# portable-atmega.net
KiCad netlist of a schematic drawn in EAGLE
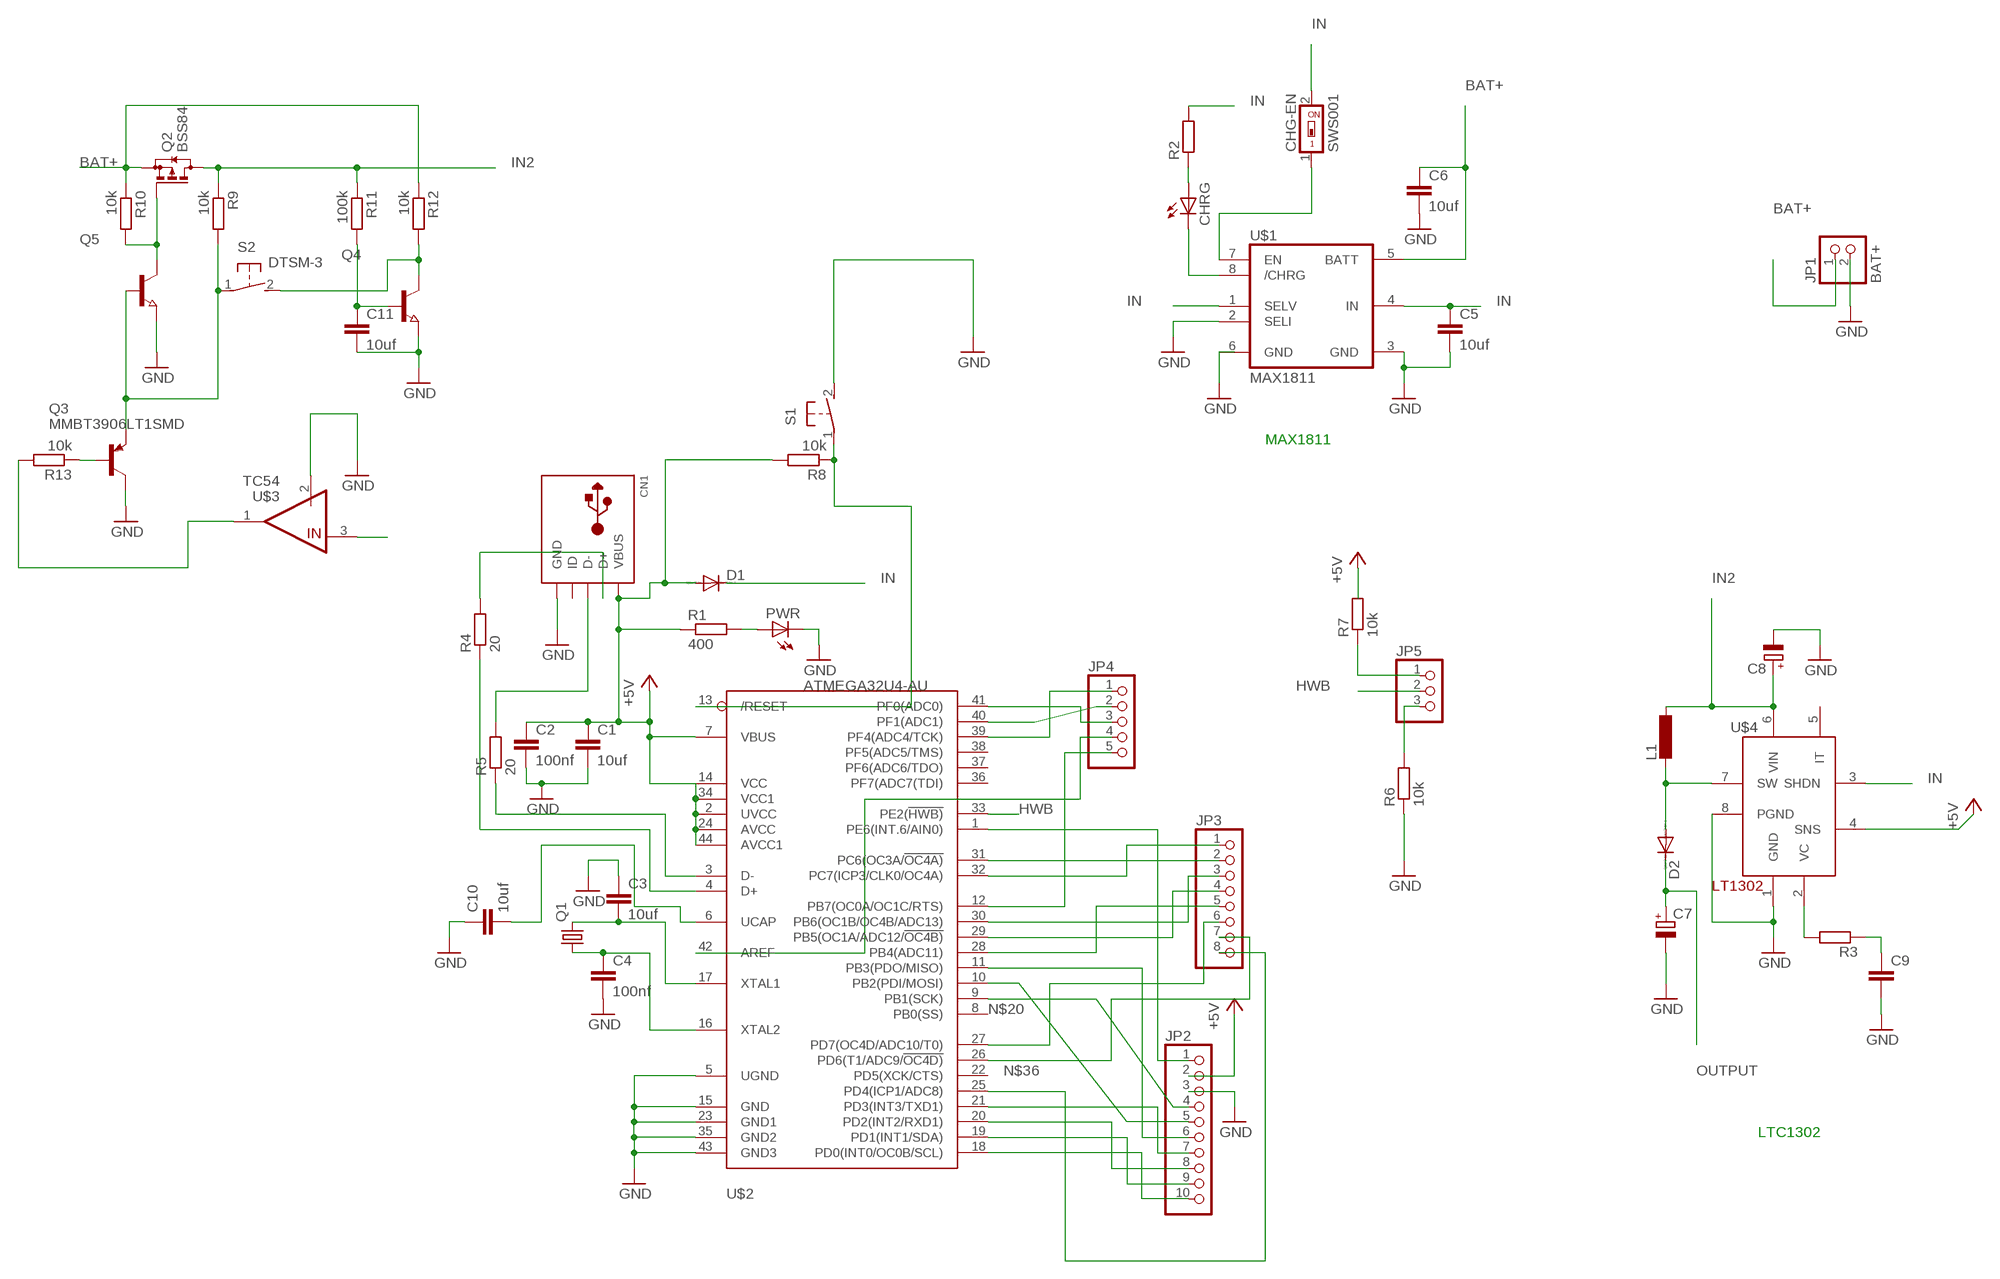
[diagram p0: schematic, sheet 1]

(export (version "E")
  (design (tool "Eeschema 10.0.6"))
  (components
    (comp (ref "C1")
      (value "10uf")
      (footprint "eagle-import:C1206")
      (libsource (lib "eagle-import") (part "C-EUC1206"))
    )
    (comp (ref "C2")
      (value "100nf")
      (footprint "eagle-import:C1206")
      (libsource (lib "eagle-import") (part "C-EUC1206"))
    )
    (comp (ref "C3")
      (value "10uf")
      (footprint "eagle-import:C1206")
      (libsource (lib "eagle-import") (part "C-EUC1206"))
    )
    (comp (ref "C4")
      (value "100nf")
      (footprint "eagle-import:C1206")
      (libsource (lib "eagle-import") (part "C-EUC1206"))
    )
    (comp (ref "C5")
      (value "10uf")
      (footprint "eagle-import:C1206")
      (libsource (lib "eagle-import") (part "C-EUC1206"))
    )
    (comp (ref "C6")
      (value "10uf")
      (footprint "eagle-import:C1206")
      (libsource (lib "eagle-import") (part "C-EUC1206"))
    )
    (comp (ref "C7")
      (value "CPOL-EUD")
      (footprint "eagle-import:PANASONIC_D")
      (libsource (lib "eagle-import") (part "CPOL-EUD"))
    )
    (comp (ref "C8")
      (value "CPOL-EUD")
      (footprint "eagle-import:PANASONIC_D")
      (libsource (lib "eagle-import") (part "CPOL-EUD"))
    )
    (comp (ref "C9")
      (value "C-EUC1206")
      (footprint "eagle-import:C1206")
      (libsource (lib "eagle-import") (part "C-EUC1206"))
    )
    (comp (ref "C10")
      (value "10uf")
      (footprint "eagle-import:C1206")
      (libsource (lib "eagle-import") (part "C-EUC1206"))
    )
    (comp (ref "C11")
      (value "10uf")
      (footprint "eagle-import:C1206")
      (libsource (lib "eagle-import") (part "C-EUC1206"))
    )
    (comp (ref "CHG-EN")
      (value "SWS001")
      (footprint "eagle-import:SMS-001")
      (libsource (lib "eagle-import") (part "SWS001"))
    )
    (comp (ref "CHRG")
      (value "LEDCHIPLED_1206")
      (footprint "eagle-import:CHIPLED_1206")
      (libsource (lib "eagle-import") (part "LEDCHIPLED_1206"))
    )
    (comp (ref "CN1")
      (value "USBMINIB")
      (footprint "eagle-import:USB-MINIB")
      (libsource (lib "eagle-import") (part "USBMINIB"))
    )
    (comp (ref "D1")
      (value "DIODE-DO214AA")
      (footprint "eagle-import:DO214AA")
      (libsource (lib "eagle-import") (part "DIODE-DO214AA"))
    )
    (comp (ref "D2")
      (value "DIODE-DO214AA")
      (footprint "eagle-import:DO214AA")
      (libsource (lib "eagle-import") (part "DIODE-DO214AA"))
    )
    (comp (ref "JP1")
      (value "BAT+")
      (footprint "eagle-import:1X02")
      (libsource (lib "eagle-import") (part "PINHD-1X2"))
    )
    (comp (ref "JP2")
      (value "PINHD-1X10")
      (footprint "eagle-import:1X10")
      (libsource (lib "eagle-import") (part "PINHD-1X10"))
    )
    (comp (ref "JP3")
      (value "PINHD-1X8")
      (footprint "eagle-import:1X08")
      (libsource (lib "eagle-import") (part "PINHD-1X8"))
    )
    (comp (ref "JP4")
      (value "PINHD-1X5")
      (footprint "eagle-import:1X05")
      (libsource (lib "eagle-import") (part "PINHD-1X5"))
    )
    (comp (ref "JP5")
      (value "PINHD-1X3")
      (footprint "eagle-import:1X03")
      (libsource (lib "eagle-import") (part "PINHD-1X3"))
    )
    (comp (ref "L1")
      (value "DO3316P")
      (footprint "eagle-import:DO3316P")
      (libsource (lib "eagle-import") (part "DO3316P"))
    )
    (comp (ref "PWR")
      (value "LEDCHIPLED_1206")
      (footprint "eagle-import:CHIPLED_1206")
      (libsource (lib "eagle-import") (part "LEDCHIPLED_1206"))
    )
    (comp (ref "Q1")
      (value "CRYSTALHC49S")
      (footprint "eagle-import:HC49_S")
      (libsource (lib "eagle-import") (part "CRYSTALHC49S"))
    )
    (comp (ref "Q2")
      (value "BSS84")
      (footprint "eagle-import:SOT23")
      (libsource (lib "eagle-import") (part "BSS84"))
    )
    (comp (ref "Q3")
      (value "MMBT3906LT1SMD")
      (footprint "eagle-import:SOT23-BEC")
      (libsource (lib "eagle-import") (part "MMBT3906SMDLT1"))
    )
    (comp (ref "Q4")
      (value "NPN-TRANSISTOR_SOT23")
      (footprint "eagle-import:SOT23")
      (libsource (lib "eagle-import") (part "NPN-TRANSISTOR_SOT23"))
    )
    (comp (ref "Q5")
      (value "NPN-TRANSISTOR_SOT23")
      (footprint "eagle-import:SOT23")
      (libsource (lib "eagle-import") (part "NPN-TRANSISTOR_SOT23"))
    )
    (comp (ref "R1")
      (value "400")
      (footprint "eagle-import:R1206")
      (libsource (lib "eagle-import") (part "R-EU_R1206"))
    )
    (comp (ref "R2")
      (value "R-EU_R1206")
      (footprint "eagle-import:R1206")
      (libsource (lib "eagle-import") (part "R-EU_R1206"))
    )
    (comp (ref "R3")
      (value "R-EU_R1206")
      (footprint "eagle-import:R1206")
      (libsource (lib "eagle-import") (part "R-EU_R1206"))
    )
    (comp (ref "R4")
      (value "20")
      (footprint "eagle-import:R1206")
      (libsource (lib "eagle-import") (part "R-EU_R1206"))
    )
    (comp (ref "R5")
      (value "20")
      (footprint "eagle-import:R1206")
      (libsource (lib "eagle-import") (part "R-EU_R1206"))
    )
    (comp (ref "R6")
      (value "10k")
      (footprint "eagle-import:R0805")
      (libsource (lib "eagle-import") (part "solar3-1_R-EU_R0805"))
    )
    (comp (ref "R7")
      (value "10k")
      (footprint "eagle-import:R0805")
      (libsource (lib "eagle-import") (part "solar3-1_R-EU_R0805"))
    )
    (comp (ref "R8")
      (value "10k")
      (footprint "eagle-import:R0805")
      (libsource (lib "eagle-import") (part "solar3-1_R-EU_R0805"))
    )
    (comp (ref "R9")
      (value "10k")
      (footprint "eagle-import:R0805")
      (libsource (lib "eagle-import") (part "solar3-1_R-EU_R0805"))
    )
    (comp (ref "R10")
      (value "10k")
      (footprint "eagle-import:R1206")
      (libsource (lib "eagle-import") (part "R-EU_R1206"))
    )
    (comp (ref "R11")
      (value "100k")
      (footprint "eagle-import:R0805")
      (libsource (lib "eagle-import") (part "solar3-1_R-EU_R0805"))
    )
    (comp (ref "R12")
      (value "10k")
      (footprint "eagle-import:R1206")
      (libsource (lib "eagle-import") (part "R-EU_R1206"))
    )
    (comp (ref "R13")
      (value "10k")
      (footprint "eagle-import:R0805")
      (libsource (lib "eagle-import") (part "solar3-1_R-EU_R0805"))
    )
    (comp (ref "S1")
      (value "31-XXSKINNY")
      (footprint "eagle-import:B3F-31XX-SKINNIER")
      (libsource (lib "eagle-import") (part "31-XXSKINNY"))
    )
    (comp (ref "S2")
      (value "DTSM-3")
      (footprint "eagle-import:DTSM-3")
      (libsource (lib "eagle-import") (part "DTSM-3"))
    )
    (comp (ref "U$1")
      (value "MAX1811")
      (footprint "eagle-import:SO08")
      (libsource (lib "eagle-import") (part "MAX1811"))
    )
    (comp (ref "U$2")
      (value "ATMEGA32U4-AU")
      (footprint "eagle-import:TQFP44")
      (libsource (lib "eagle-import") (part "ATMEGA32U4-AU"))
    )
    (comp (ref "U$3")
      (value "TC54")
      (footprint "eagle-import:SOT23-3")
      (libsource (lib "eagle-import") (part "TC54"))
    )
    (comp (ref "U$4")
      (value "LT1302SO8")
      (footprint "eagle-import:SO08")
      (libsource (lib "eagle-import") (part "LT1302SO8"))
    )
  )
  (nets
    (net (code "1") (name "+5V") (class "Default")
      (node (ref "C1") (pin "1") (pinfunction "1_1") (pintype "passive"))
      (node (ref "C2") (pin "1") (pinfunction "1_1") (pintype "passive"))
      (node (ref "CN1") (pin "VBUS") (pinfunction "VBUS_VBUS") (pintype "power_in"))
      (node (ref "D1") (pin "A") (pinfunction "A_A") (pintype "passive"))
      (node (ref "JP2") (pin "2") (pinfunction "2_2") (pintype "passive"))
      (node (ref "R1") (pin "1") (pinfunction "1_1") (pintype "passive"))
      (node (ref "R7") (pin "2") (pinfunction "2_2") (pintype "passive"))
      (node (ref "R8") (pin "2") (pinfunction "2_2") (pintype "passive"))
      (node (ref "U$2") (pin "14") (pinfunction "VCC_14") (pintype "bidirectional"))
      (node (ref "U$2") (pin "2") (pinfunction "UVCC_2") (pintype "bidirectional"))
      (node (ref "U$2") (pin "24") (pinfunction "AVCC_24") (pintype "bidirectional"))
      (node (ref "U$2") (pin "34") (pinfunction "VCC1_34") (pintype "bidirectional"))
      (node (ref "U$2") (pin "44") (pinfunction "AVCC1_44") (pintype "bidirectional"))
      (node (ref "U$2") (pin "7") (pinfunction "VBUS_7") (pintype "bidirectional"))
      (node (ref "U$4") (pin "4") (pinfunction "SNS_4") (pintype "passive"))
    )
    (net (code "2") (name "/BAT+") (class "Default")
      (node (ref "C6") (pin "1") (pinfunction "1_1") (pintype "passive"))
      (node (ref "JP1") (pin "1") (pinfunction "1_1") (pintype "passive"))
      (node (ref "Q2") (pin "2") (pinfunction "S_2") (pintype "passive"))
      (node (ref "R10") (pin "1") (pinfunction "1_1") (pintype "passive"))
      (node (ref "R12") (pin "1") (pinfunction "1_1") (pintype "passive"))
      (node (ref "U$1") (pin "5") (pinfunction "BATT_5") (pintype "output"))
      (node (ref "U$3") (pin "3") (pinfunction "VIN_3") (pintype "input"))
    )
    (net (code "3") (name "/HWB") (class "Default")
      (node (ref "JP5") (pin "2") (pinfunction "2_2") (pintype "passive"))
      (node (ref "U$2") (pin "33") (pinfunction "PE2(~{HWB})_33") (pintype "bidirectional"))
    )
    (net (code "4") (name "/IN") (class "Default")
      (node (ref "C5") (pin "1") (pinfunction "1_1") (pintype "passive"))
      (node (ref "CHG-EN") (pin "2") (pinfunction "2_2") (pintype "passive"))
      (node (ref "D1") (pin "C") (pinfunction "C_C") (pintype "passive"))
      (node (ref "R2") (pin "2") (pinfunction "2_2") (pintype "passive"))
      (node (ref "U$1") (pin "1") (pinfunction "SELV_1") (pintype "input"))
      (node (ref "U$1") (pin "4") (pinfunction "IN_4") (pintype "power_in"))
      (node (ref "U$4") (pin "3") (pinfunction "SHDN_3") (pintype "input"))
    )
    (net (code "5") (name "/IN2") (class "Default")
      (node (ref "C8") (pin "+") (pinfunction "+_+") (pintype "passive"))
      (node (ref "L1") (pin "2") (pinfunction "2_2") (pintype "passive"))
      (node (ref "Q2") (pin "3") (pinfunction "D_3") (pintype "passive"))
      (node (ref "R11") (pin "1") (pinfunction "1_1") (pintype "passive"))
      (node (ref "R9") (pin "1") (pinfunction "1_1") (pintype "passive"))
      (node (ref "U$4") (pin "6") (pinfunction "VIN_6") (pintype "input"))
    )
    (net (code "6") (name "/N$20") (class "Default")
      (node (ref "JP2") (pin "4") (pinfunction "4_4") (pintype "passive"))
      (node (ref "U$2") (pin "9") (pinfunction "PB1(SCK)_9") (pintype "bidirectional"))
    )
    (net (code "7") (name "/N$36") (class "Default")
      (node (ref "JP3") (pin "7") (pinfunction "7_7") (pintype "passive"))
      (node (ref "U$2") (pin "26") (pinfunction "PD6(T1/ADC9/~{OC4D})_26") (pintype "bidirectional"))
    )
    (net (code "8") (name "/OUTPUT") (class "Default")
      (node (ref "C7") (pin "+") (pinfunction "+_+") (pintype "passive"))
      (node (ref "D2") (pin "C") (pinfunction "C_C") (pintype "passive"))
    )
    (net (code "9") (name "GND") (class "Default")
      (node (ref "C1") (pin "2") (pinfunction "2_2") (pintype "passive"))
      (node (ref "C10") (pin "1") (pinfunction "1_1") (pintype "passive"))
      (node (ref "C11") (pin "2") (pinfunction "2_2") (pintype "passive"))
      (node (ref "C2") (pin "2") (pinfunction "2_2") (pintype "passive"))
      (node (ref "C3") (pin "1") (pinfunction "1_1") (pintype "passive"))
      (node (ref "C4") (pin "2") (pinfunction "2_2") (pintype "passive"))
      (node (ref "C5") (pin "2") (pinfunction "2_2") (pintype "passive"))
      (node (ref "C6") (pin "2") (pinfunction "2_2") (pintype "passive"))
      (node (ref "C7") (pin "-") (pinfunction "-_-") (pintype "passive"))
      (node (ref "C8") (pin "-") (pinfunction "-_-") (pintype "passive"))
      (node (ref "C9") (pin "2") (pinfunction "2_2") (pintype "passive"))
      (node (ref "CN1") (pin "GND") (pinfunction "GND_GND") (pintype "power_in"))
      (node (ref "JP1") (pin "2") (pinfunction "2_2") (pintype "passive"))
      (node (ref "JP2") (pin "3") (pinfunction "3_3") (pintype "passive"))
      (node (ref "PWR") (pin "C") (pinfunction "C_C") (pintype "passive"))
      (node (ref "Q3") (pin "C") (pinfunction "C_C") (pintype "passive"))
      (node (ref "Q4") (pin "2") (pinfunction "E_2") (pintype "passive"))
      (node (ref "Q5") (pin "2") (pinfunction "E_2") (pintype "passive"))
      (node (ref "R6") (pin "1") (pinfunction "1_1") (pintype "passive"))
      (node (ref "S1") (pin "2") (pinfunction "S_2") (pintype "passive"))
      (node (ref "U$1") (pin "2") (pinfunction "SELI_2") (pintype "input"))
      (node (ref "U$1") (pin "3") (pinfunction "GND_3") (pintype "power_in"))
      (node (ref "U$1") (pin "6") (pinfunction "GND_6") (pintype "power_in"))
      (node (ref "U$2") (pin "15") (pinfunction "GND_15") (pintype "bidirectional"))
      (node (ref "U$2") (pin "23") (pinfunction "GND1_23") (pintype "bidirectional"))
      (node (ref "U$2") (pin "35") (pinfunction "GND2_35") (pintype "bidirectional"))
      (node (ref "U$2") (pin "43") (pinfunction "GND3_43") (pintype "bidirectional"))
      (node (ref "U$2") (pin "5") (pinfunction "UGND_5") (pintype "bidirectional"))
      (node (ref "U$3") (pin "2") (pinfunction "VSS_2") (pintype "power_in"))
      (node (ref "U$4") (pin "1") (pinfunction "GND_1") (pintype "input"))
      (node (ref "U$4") (pin "8") (pinfunction "PGND_8") (pintype "input"))
    )
    (net (code "10") (name "Net-(C9-Pad1)") (class "Default")
      (node (ref "C9") (pin "1") (pinfunction "1_1") (pintype "passive"))
      (node (ref "R3") (pin "1") (pinfunction "1_1") (pintype "passive"))
    )
    (net (code "11") (name "Net-(CHRG-PadA)") (class "Default")
      (node (ref "CHRG") (pin "A") (pinfunction "A_A") (pintype "passive"))
      (node (ref "R2") (pin "1") (pinfunction "1_1") (pintype "passive"))
    )
    (net (code "12") (name "Net-(CN1-PadD+)") (class "Default")
      (node (ref "CN1") (pin "D+") (pinfunction "D+_D+") (pintype "bidirectional"))
      (node (ref "R4") (pin "2") (pinfunction "2_2") (pintype "passive"))
    )
    (net (code "13") (name "Net-(CN1-PadD-)") (class "Default")
      (node (ref "CN1") (pin "D-") (pinfunction "D-_D-") (pintype "bidirectional"))
      (node (ref "R5") (pin "2") (pinfunction "2_2") (pintype "passive"))
    )
    (net (code "14") (name "Net-(JP5-Pad1)") (class "Default")
      (node (ref "JP5") (pin "1") (pinfunction "1_1") (pintype "passive"))
      (node (ref "R7") (pin "1") (pinfunction "1_1") (pintype "passive"))
    )
    (net (code "15") (name "Net-(JP5-Pad3)") (class "Default")
      (node (ref "JP5") (pin "3") (pinfunction "3_3") (pintype "passive"))
      (node (ref "R6") (pin "2") (pinfunction "2_2") (pintype "passive"))
    )
    (net (code "16") (name "Net-(PWR-PadA)") (class "Default")
      (node (ref "PWR") (pin "A") (pinfunction "A_A") (pintype "passive"))
      (node (ref "R1") (pin "2") (pinfunction "2_2") (pintype "passive"))
    )
    (net (code "17") (name "Net-(Q2-G)") (class "Default")
      (node (ref "Q2") (pin "1") (pinfunction "G_1") (pintype "passive"))
      (node (ref "Q5") (pin "3") (pinfunction "C_3") (pintype "passive"))
      (node (ref "R10") (pin "2") (pinfunction "2_2") (pintype "passive"))
    )
    (net (code "18") (name "Net-(Q3-PadB)") (class "Default")
      (node (ref "Q3") (pin "B") (pinfunction "B_B") (pintype "passive"))
      (node (ref "R13") (pin "1") (pinfunction "1_1") (pintype "passive"))
    )
    (net (code "19") (name "Net-(Q4-B)") (class "Default")
      (node (ref "C11") (pin "1") (pinfunction "1_1") (pintype "passive"))
      (node (ref "Q4") (pin "1") (pinfunction "B_1") (pintype "passive"))
      (node (ref "R11") (pin "2") (pinfunction "2_2") (pintype "passive"))
    )
    (net (code "20") (name "Net-(Q4-C)") (class "Default")
      (node (ref "Q4") (pin "3") (pinfunction "C_3") (pintype "passive"))
      (node (ref "R12") (pin "2") (pinfunction "2_2") (pintype "passive"))
      (node (ref "S2") (pin "2") (pinfunction "2_2") (pintype "passive"))
    )
    (net (code "21") (name "Net-(Q5-B)") (class "Default")
      (node (ref "Q3") (pin "E") (pinfunction "E_E") (pintype "passive"))
      (node (ref "Q5") (pin "1") (pinfunction "B_1") (pintype "passive"))
      (node (ref "R9") (pin "2") (pinfunction "2_2") (pintype "passive"))
      (node (ref "S2") (pin "1") (pinfunction "1_1") (pintype "passive"))
    )
    (net (code "22") (name "Net-(S1-P)") (class "Default")
      (node (ref "R8") (pin "1") (pinfunction "1_1") (pintype "passive"))
      (node (ref "S1") (pin "1") (pinfunction "P_1") (pintype "passive"))
      (node (ref "U$2") (pin "13") (pinfunction "/RESET_13") (pintype "bidirectional"))
    )
    (net (code "23") (name "Net-(U$1-EN)") (class "Default")
      (node (ref "CHG-EN") (pin "1") (pinfunction "1_1") (pintype "passive"))
      (node (ref "U$1") (pin "7") (pinfunction "EN_7") (pintype "input"))
    )
    (net (code "24") (name "Net-(U$1-{slash}CHRG)") (class "Default")
      (node (ref "CHRG") (pin "C") (pinfunction "C_C") (pintype "passive"))
      (node (ref "U$1") (pin "8") (pinfunction "/CHRG_8") (pintype "output"))
    )
    (net (code "25") (name "Net-(U$2-AREF)") (class "Default")
      (node (ref "JP4") (pin "4") (pinfunction "4_4") (pintype "passive"))
      (node (ref "U$2") (pin "42") (pinfunction "AREF_42") (pintype "bidirectional"))
    )
    (net (code "26") (name "Net-(U$2-D+)") (class "Default")
      (node (ref "R4") (pin "1") (pinfunction "1_1") (pintype "passive"))
      (node (ref "U$2") (pin "4") (pinfunction "D+_4") (pintype "bidirectional"))
    )
    (net (code "27") (name "Net-(U$2-D-)") (class "Default")
      (node (ref "R5") (pin "1") (pinfunction "1_1") (pintype "passive"))
      (node (ref "U$2") (pin "3") (pinfunction "D-_3") (pintype "bidirectional"))
    )
    (net (code "28") (name "Net-(U$2-PB2(PDI{slash}MOSI))") (class "Default")
      (node (ref "JP2") (pin "5") (pinfunction "5_5") (pintype "passive"))
      (node (ref "U$2") (pin "10") (pinfunction "PB2(PDI/MOSI)_10") (pintype "bidirectional"))
    )
    (net (code "29") (name "Net-(U$2-PB3(PDO{slash}MISO))") (class "Default")
      (node (ref "JP2") (pin "6") (pinfunction "6_6") (pintype "passive"))
      (node (ref "U$2") (pin "11") (pinfunction "PB3(PDO/MISO)_11") (pintype "bidirectional"))
    )
    (net (code "30") (name "Net-(U$2-PB4(ADC11))") (class "Default")
      (node (ref "JP3") (pin "5") (pinfunction "5_5") (pintype "passive"))
      (node (ref "U$2") (pin "28") (pinfunction "PB4(ADC11)_28") (pintype "bidirectional"))
    )
    (net (code "31") (name "Net-(U$2-PB5(OC1A{slash}ADC12{slash}~{OC4B}))") (class "Default")
      (node (ref "JP3") (pin "4") (pinfunction "4_4") (pintype "passive"))
      (node (ref "U$2") (pin "29") (pinfunction "PB5(OC1A/ADC12/~{OC4B})_29") (pintype "bidirectional"))
    )
    (net (code "32") (name "Net-(U$2-PB6(OC1B{slash}OC4B{slash}ADC13))") (class "Default")
      (node (ref "JP3") (pin "3") (pinfunction "3_3") (pintype "passive"))
      (node (ref "U$2") (pin "30") (pinfunction "PB6(OC1B/OC4B/ADC13)_30") (pintype "bidirectional"))
    )
    (net (code "33") (name "Net-(U$2-PB7(OC0A{slash}OC1C{slash}RTS))") (class "Default")
      (node (ref "JP4") (pin "5") (pinfunction "5_5") (pintype "passive"))
      (node (ref "U$2") (pin "12") (pinfunction "PB7(OC0A/OC1C/RTS)_12") (pintype "bidirectional"))
    )
    (net (code "34") (name "Net-(U$2-PC6(OC3A{slash}~{OC4A}))") (class "Default")
      (node (ref "JP3") (pin "2") (pinfunction "2_2") (pintype "passive"))
      (node (ref "U$2") (pin "31") (pinfunction "PC6(OC3A/~{OC4A})_31") (pintype "bidirectional"))
    )
    (net (code "35") (name "Net-(U$2-PC7(ICP3{slash}CLK0{slash}OC4A))") (class "Default")
      (node (ref "JP3") (pin "1") (pinfunction "1_1") (pintype "passive"))
      (node (ref "U$2") (pin "32") (pinfunction "PC7(ICP3/CLK0/OC4A)_32") (pintype "bidirectional"))
    )
    (net (code "36") (name "Net-(U$2-PD0(INT0{slash}OC0B{slash}SCL))") (class "Default")
      (node (ref "JP2") (pin "10") (pinfunction "10_10") (pintype "passive"))
      (node (ref "U$2") (pin "18") (pinfunction "PD0(INT0/OC0B/SCL)_18") (pintype "bidirectional"))
    )
    (net (code "37") (name "Net-(U$2-PD1(INT1{slash}SDA))") (class "Default")
      (node (ref "JP2") (pin "9") (pinfunction "9_9") (pintype "passive"))
      (node (ref "U$2") (pin "19") (pinfunction "PD1(INT1/SDA)_19") (pintype "bidirectional"))
    )
    (net (code "38") (name "Net-(U$2-PD2(INT2{slash}RXD1))") (class "Default")
      (node (ref "JP2") (pin "8") (pinfunction "8_8") (pintype "passive"))
      (node (ref "U$2") (pin "20") (pinfunction "PD2(INT2/RXD1)_20") (pintype "bidirectional"))
    )
    (net (code "39") (name "Net-(U$2-PD3(INT3{slash}TXD1))") (class "Default")
      (node (ref "JP2") (pin "7") (pinfunction "7_7") (pintype "passive"))
      (node (ref "U$2") (pin "21") (pinfunction "PD3(INT3/TXD1)_21") (pintype "bidirectional"))
    )
    (net (code "40") (name "Net-(U$2-PD4(ICP1{slash}ADC8))") (class "Default")
      (node (ref "JP3") (pin "8") (pinfunction "8_8") (pintype "passive"))
      (node (ref "U$2") (pin "25") (pinfunction "PD4(ICP1/ADC8)_25") (pintype "bidirectional"))
    )
    (net (code "41") (name "Net-(U$2-PD7(OC4D{slash}ADC10{slash}T0))") (class "Default")
      (node (ref "JP3") (pin "6") (pinfunction "6_6") (pintype "passive"))
      (node (ref "U$2") (pin "27") (pinfunction "PD7(OC4D/ADC10/T0)_27") (pintype "bidirectional"))
    )
    (net (code "42") (name "Net-(U$2-PE6(INT.6{slash}AIN0))") (class "Default")
      (node (ref "JP2") (pin "1") (pinfunction "1_1") (pintype "passive"))
      (node (ref "U$2") (pin "1") (pinfunction "PE6(INT.6/AIN0)_1") (pintype "bidirectional"))
    )
    (net (code "43") (name "Net-(U$2-PF0(ADC0))") (class "Default")
      (node (ref "JP4") (pin "3") (pinfunction "3_3") (pintype "passive"))
      (node (ref "U$2") (pin "41") (pinfunction "PF0(ADC0)_41") (pintype "bidirectional"))
    )
    (net (code "44") (name "Net-(U$2-PF1(ADC1))") (class "Default")
      (node (ref "JP4") (pin "2") (pinfunction "2_2") (pintype "passive"))
      (node (ref "U$2") (pin "40") (pinfunction "PF1(ADC1)_40") (pintype "bidirectional"))
    )
    (net (code "45") (name "Net-(U$2-PF4(ADC4{slash}TCK))") (class "Default")
      (node (ref "JP4") (pin "1") (pinfunction "1_1") (pintype "passive"))
      (node (ref "U$2") (pin "39") (pinfunction "PF4(ADC4/TCK)_39") (pintype "bidirectional"))
    )
    (net (code "46") (name "Net-(U$2-UCAP)") (class "Default")
      (node (ref "C10") (pin "2") (pinfunction "2_2") (pintype "passive"))
      (node (ref "U$2") (pin "6") (pinfunction "UCAP_6") (pintype "bidirectional"))
    )
    (net (code "47") (name "Net-(U$2-XTAL1)") (class "Default")
      (node (ref "C3") (pin "2") (pinfunction "2_2") (pintype "passive"))
      (node (ref "Q1") (pin "2") (pinfunction "2_2") (pintype "passive"))
      (node (ref "U$2") (pin "17") (pinfunction "XTAL1_17") (pintype "bidirectional"))
    )
    (net (code "48") (name "Net-(U$2-XTAL2)") (class "Default")
      (node (ref "C4") (pin "1") (pinfunction "1_1") (pintype "passive"))
      (node (ref "Q1") (pin "1") (pinfunction "1_1") (pintype "passive"))
      (node (ref "U$2") (pin "16") (pinfunction "XTAL2_16") (pintype "bidirectional"))
    )
    (net (code "49") (name "Net-(U$3-VOUT)") (class "Default")
      (node (ref "R13") (pin "2") (pinfunction "2_2") (pintype "passive"))
      (node (ref "U$3") (pin "1") (pinfunction "VOUT_1") (pintype "output"))
    )
    (net (code "50") (name "Net-(U$4-SW)") (class "Default")
      (node (ref "D2") (pin "A") (pinfunction "A_A") (pintype "passive"))
      (node (ref "L1") (pin "1") (pinfunction "1_1") (pintype "passive"))
      (node (ref "U$4") (pin "7") (pinfunction "SW_7") (pintype "input"))
    )
    (net (code "51") (name "Net-(U$4-VC)") (class "Default")
      (node (ref "R3") (pin "2") (pinfunction "2_2") (pintype "passive"))
      (node (ref "U$4") (pin "2") (pinfunction "VC_2") (pintype "passive"))
    )
    (net (code "52") (name "unconnected-(CN1-PadID)") (class "Default")
      (node (ref "CN1") (pin "ID") (pinfunction "ID_ID") (pintype "bidirectional"))
    )
    (net (code "53") (name "unconnected-(U$2-PB0(SS)-Pad8)") (class "Default")
      (node (ref "U$2") (pin "8") (pinfunction "PB0(SS)_8") (pintype "bidirectional"))
    )
    (net (code "54") (name "unconnected-(U$2-PD5(XCK{slash}CTS)-Pad22)") (class "Default")
      (node (ref "U$2") (pin "22") (pinfunction "PD5(XCK/CTS)_22") (pintype "bidirectional"))
    )
    (net (code "55") (name "unconnected-(U$2-PF5(ADC5{slash}TMS)-Pad38)") (class "Default")
      (node (ref "U$2") (pin "38") (pinfunction "PF5(ADC5/TMS)_38") (pintype "bidirectional"))
    )
    (net (code "56") (name "unconnected-(U$2-PF6(ADC6{slash}TDO)-Pad37)") (class "Default")
      (node (ref "U$2") (pin "37") (pinfunction "PF6(ADC6/TDO)_37") (pintype "bidirectional"))
    )
    (net (code "57") (name "unconnected-(U$2-PF7(ADC7(TDI)-Pad36)") (class "Default")
      (node (ref "U$2") (pin "36") (pinfunction "PF7(ADC7(TDI)_36") (pintype "bidirectional"))
    )
    (net (code "58") (name "unconnected-(U$4-IT-Pad5)") (class "Default")
      (node (ref "U$4") (pin "5") (pinfunction "IT_5") (pintype "input"))
    )
  )
)
